# motor_board.net
KiCad netlist of a schematic drawn in EAGLE
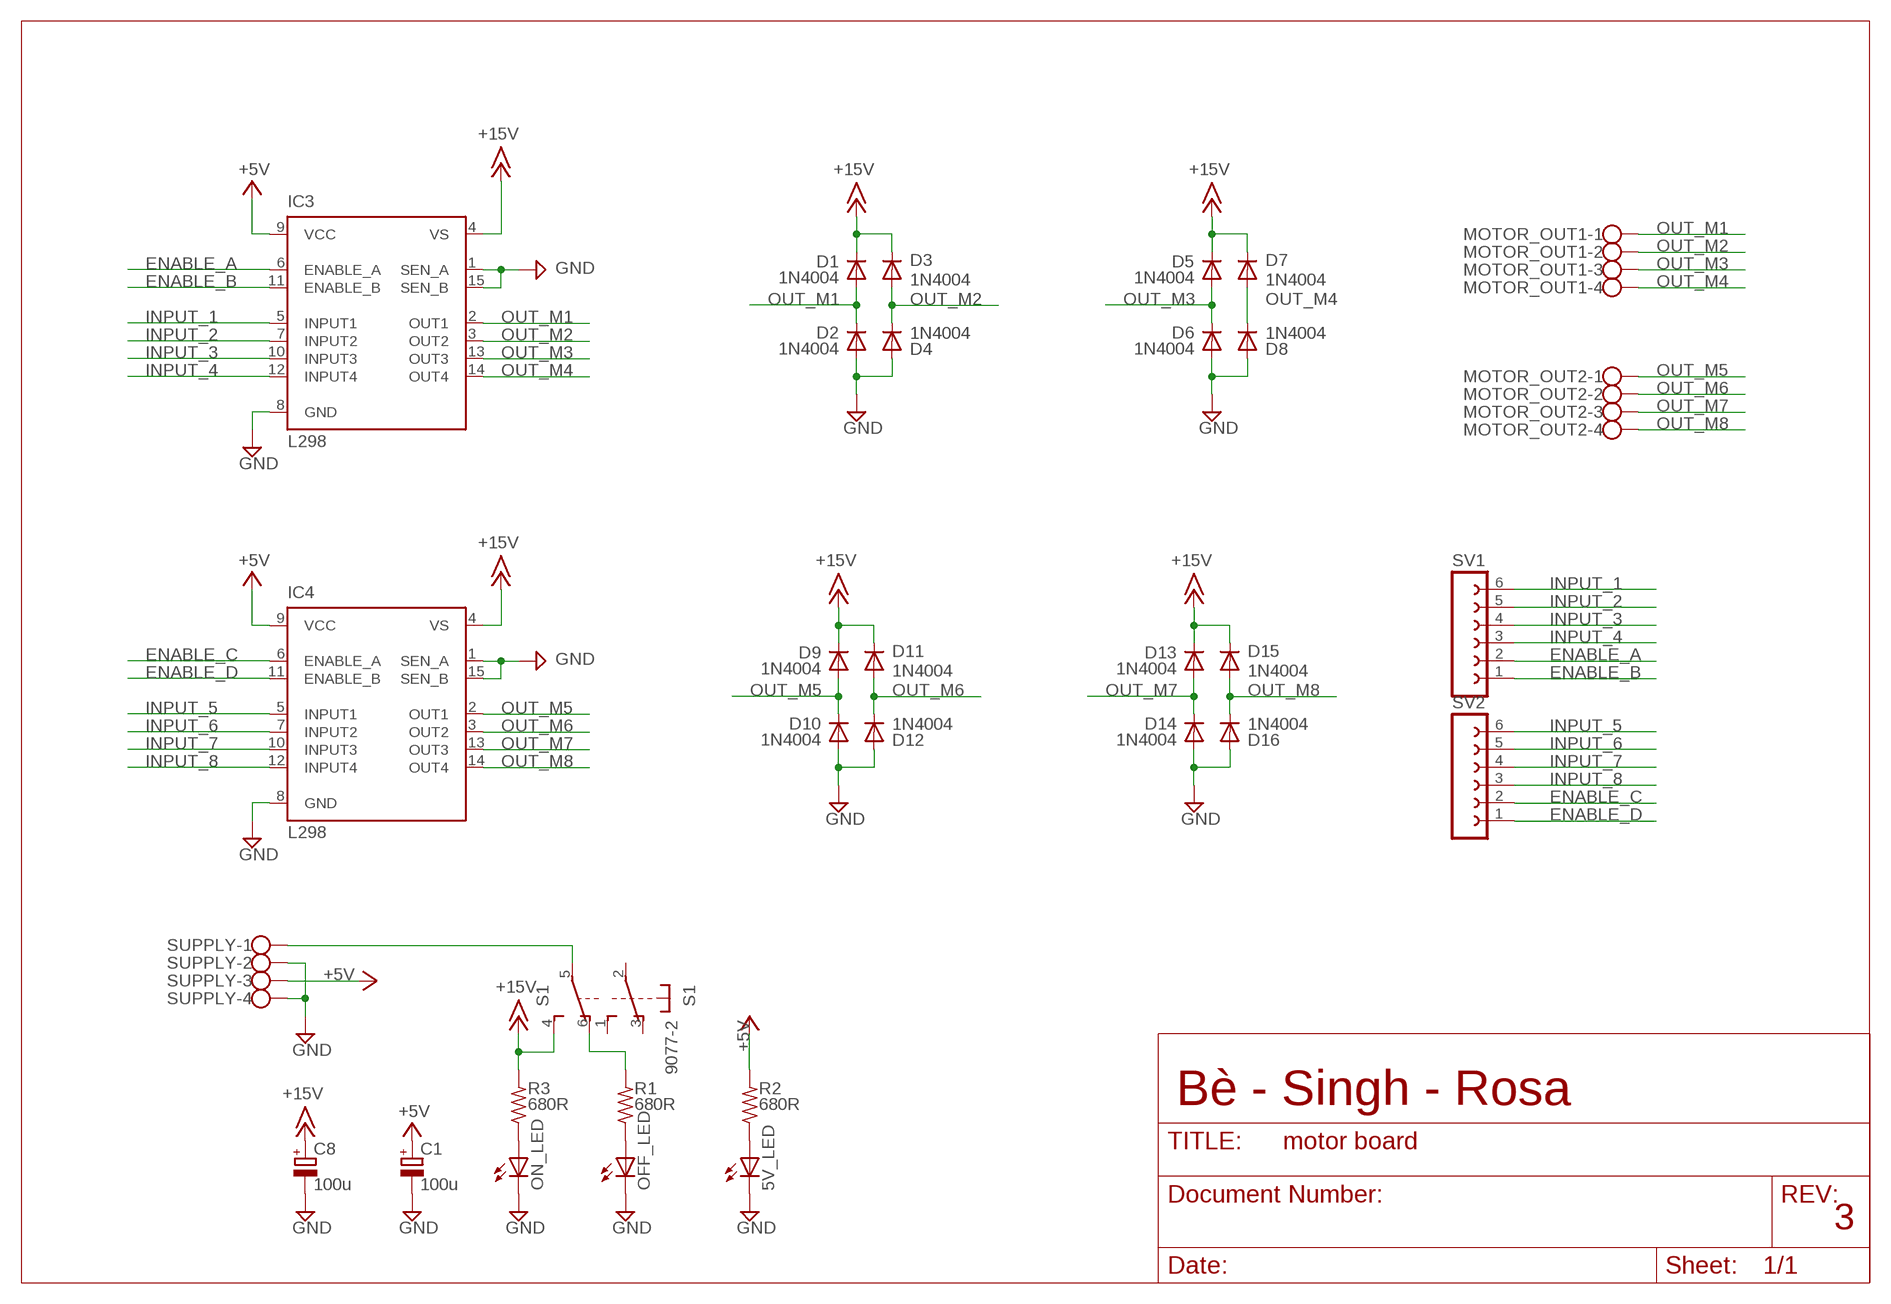
[diagram p0: schematic, sheet 1]

(export (version "E")
  (design (tool "Eeschema 10.0.6"))
  (components
    (comp (ref "5V_LED")
      (value "LED5MM")
      (footprint "eagle-import:LED5MM")
      (libsource (lib "eagle-import") (part "LED5MM"))
    )
    (comp (ref "C1")
      (value "100u")
      (footprint "eagle-import:E2,5-7")
      (libsource (lib "eagle-import") (part "CPOL-EUE2.5-7"))
    )
    (comp (ref "C8")
      (value "100u")
      (footprint "eagle-import:E3,5-8")
      (libsource (lib "eagle-import") (part "rcl_CPOL-EUE3.5-8"))
    )
    (comp (ref "D1")
      (value "1N4004")
      (footprint "eagle-import:DO41-10")
      (libsource (lib "eagle-import") (part "1N4004"))
    )
    (comp (ref "D2")
      (value "1N4004")
      (footprint "eagle-import:DO41-10")
      (libsource (lib "eagle-import") (part "1N4004"))
    )
    (comp (ref "D3")
      (value "1N4004")
      (footprint "eagle-import:DO41-10")
      (libsource (lib "eagle-import") (part "1N4004"))
    )
    (comp (ref "D4")
      (value "1N4004")
      (footprint "eagle-import:DO41-10")
      (libsource (lib "eagle-import") (part "1N4004"))
    )
    (comp (ref "D5")
      (value "1N4004")
      (footprint "eagle-import:DO41-10")
      (libsource (lib "eagle-import") (part "1N4004"))
    )
    (comp (ref "D6")
      (value "1N4004")
      (footprint "eagle-import:DO41-10")
      (libsource (lib "eagle-import") (part "1N4004"))
    )
    (comp (ref "D7")
      (value "1N4004")
      (footprint "eagle-import:DO41-10")
      (libsource (lib "eagle-import") (part "1N4004"))
    )
    (comp (ref "D8")
      (value "1N4004")
      (footprint "eagle-import:DO41-10")
      (libsource (lib "eagle-import") (part "1N4004"))
    )
    (comp (ref "D9")
      (value "1N4004")
      (footprint "eagle-import:DO41-10")
      (libsource (lib "eagle-import") (part "1N4004"))
    )
    (comp (ref "D10")
      (value "1N4004")
      (footprint "eagle-import:DO41-10")
      (libsource (lib "eagle-import") (part "1N4004"))
    )
    (comp (ref "D11")
      (value "1N4004")
      (footprint "eagle-import:DO41-10")
      (libsource (lib "eagle-import") (part "1N4004"))
    )
    (comp (ref "D12")
      (value "1N4004")
      (footprint "eagle-import:DO41-10")
      (libsource (lib "eagle-import") (part "1N4004"))
    )
    (comp (ref "D13")
      (value "1N4004")
      (footprint "eagle-import:DO41-10")
      (libsource (lib "eagle-import") (part "1N4004"))
    )
    (comp (ref "D14")
      (value "1N4004")
      (footprint "eagle-import:DO41-10")
      (libsource (lib "eagle-import") (part "1N4004"))
    )
    (comp (ref "D15")
      (value "1N4004")
      (footprint "eagle-import:DO41-10")
      (libsource (lib "eagle-import") (part "1N4004"))
    )
    (comp (ref "D16")
      (value "1N4004")
      (footprint "eagle-import:DO41-10")
      (libsource (lib "eagle-import") (part "1N4004"))
    )
    (comp (ref "IC3")
      (value "L298")
      (footprint "eagle-import:MULTIWATT-15")
      (libsource (lib "eagle-import") (part "L298"))
    )
    (comp (ref "IC4")
      (value "L298")
      (footprint "eagle-import:MULTIWATT-15")
      (libsource (lib "eagle-import") (part "L298"))
    )
    (comp (ref "MOTOR_OUT1")
      (value "W237-4")
      (footprint "eagle-import:W237-4")
      (libsource (lib "eagle-import") (part "W237-4"))
    )
    (comp (ref "MOTOR_OUT2")
      (value "W237-4")
      (footprint "eagle-import:W237-4")
      (libsource (lib "eagle-import") (part "W237-4"))
    )
    (comp (ref "OFF_LED")
      (value "LED5MM")
      (footprint "eagle-import:LED5MM")
      (libsource (lib "eagle-import") (part "LED5MM"))
    )
    (comp (ref "ON_LED")
      (value "LED5MM")
      (footprint "eagle-import:LED5MM")
      (libsource (lib "eagle-import") (part "LED5MM"))
    )
    (comp (ref "R1")
      (value "680R")
      (footprint "eagle-import:0207_10")
      (libsource (lib "eagle-import") (part "R-US_0207/10"))
    )
    (comp (ref "R2")
      (value "680R")
      (footprint "eagle-import:0207_10")
      (libsource (lib "eagle-import") (part "R-US_0207/10"))
    )
    (comp (ref "R3")
      (value "680R")
      (footprint "eagle-import:0207_10")
      (libsource (lib "eagle-import") (part "R-US_0207/10"))
    )
    (comp (ref "S1")
      (value "9077-2")
      (footprint "eagle-import:9077-2")
      (libsource (lib "eagle-import") (part "9077-2"))
    )
    (comp (ref "SUPPLY")
      (value "W237-4")
      (footprint "eagle-import:W237-4")
      (libsource (lib "eagle-import") (part "W237-4"))
    )
    (comp (ref "SV1")
      (value "FE06-1")
      (footprint "eagle-import:FE06")
      (libsource (lib "eagle-import") (part "FE06-1"))
    )
    (comp (ref "SV2")
      (value "FE06-1")
      (footprint "eagle-import:FE06")
      (libsource (lib "eagle-import") (part "FE06-1"))
    )
  )
  (nets
    (net (code "1") (name "+5V") (class "Default")
      (node (ref "C1") (pin "+") (pinfunction "+_+") (pintype "passive"))
      (node (ref "IC3") (pin "9") (pinfunction "VCC_9") (pintype "power_in"))
      (node (ref "IC4") (pin "9") (pinfunction "VCC_9") (pintype "power_in"))
      (node (ref "R2") (pin "2") (pinfunction "2_2") (pintype "passive"))
      (node (ref "SUPPLY") (pin "3") (pinfunction "KL_3") (pintype "passive"))
    )
    (net (code "2") (name "+15V") (class "Default")
      (node (ref "C8") (pin "+") (pinfunction "+_+") (pintype "passive"))
      (node (ref "D1") (pin "C") (pinfunction "C_C") (pintype "passive"))
      (node (ref "D11") (pin "C") (pinfunction "C_C") (pintype "passive"))
      (node (ref "D13") (pin "C") (pinfunction "C_C") (pintype "passive"))
      (node (ref "D15") (pin "C") (pinfunction "C_C") (pintype "passive"))
      (node (ref "D3") (pin "C") (pinfunction "C_C") (pintype "passive"))
      (node (ref "D5") (pin "C") (pinfunction "C_C") (pintype "passive"))
      (node (ref "D7") (pin "C") (pinfunction "C_C") (pintype "passive"))
      (node (ref "D9") (pin "C") (pinfunction "C_C") (pintype "passive"))
      (node (ref "IC3") (pin "4") (pinfunction "VS_4") (pintype "power_in"))
      (node (ref "IC4") (pin "4") (pinfunction "VS_4") (pintype "power_in"))
      (node (ref "R3") (pin "2") (pinfunction "2_2") (pintype "passive"))
      (node (ref "S1") (pin "4") (pinfunction "S_4") (pintype "passive"))
    )
    (net (code "3") (name "/ENABLE_A") (class "Default")
      (node (ref "IC3") (pin "6") (pinfunction "ENABLE_A_6") (pintype "input"))
      (node (ref "SV1") (pin "2") (pinfunction "2_2") (pintype "passive"))
    )
    (net (code "4") (name "/ENABLE_B") (class "Default")
      (node (ref "IC3") (pin "11") (pinfunction "ENABLE_B_11") (pintype "input"))
      (node (ref "SV1") (pin "1") (pinfunction "1_1") (pintype "passive"))
    )
    (net (code "5") (name "/ENABLE_C") (class "Default")
      (node (ref "IC4") (pin "6") (pinfunction "ENABLE_A_6") (pintype "input"))
      (node (ref "SV2") (pin "2") (pinfunction "2_2") (pintype "passive"))
    )
    (net (code "6") (name "/ENABLE_D") (class "Default")
      (node (ref "IC4") (pin "11") (pinfunction "ENABLE_B_11") (pintype "input"))
      (node (ref "SV2") (pin "1") (pinfunction "1_1") (pintype "passive"))
    )
    (net (code "7") (name "/INPUT_1") (class "Default")
      (node (ref "IC3") (pin "5") (pinfunction "INPUT1_5") (pintype "input"))
      (node (ref "SV1") (pin "6") (pinfunction "6_6") (pintype "passive"))
    )
    (net (code "8") (name "/INPUT_2") (class "Default")
      (node (ref "IC3") (pin "7") (pinfunction "INPUT2_7") (pintype "input"))
      (node (ref "SV1") (pin "5") (pinfunction "5_5") (pintype "passive"))
    )
    (net (code "9") (name "/INPUT_3") (class "Default")
      (node (ref "IC3") (pin "10") (pinfunction "INPUT3_10") (pintype "input"))
      (node (ref "SV1") (pin "4") (pinfunction "4_4") (pintype "passive"))
    )
    (net (code "10") (name "/INPUT_4") (class "Default")
      (node (ref "IC3") (pin "12") (pinfunction "INPUT4_12") (pintype "input"))
      (node (ref "SV1") (pin "3") (pinfunction "3_3") (pintype "passive"))
    )
    (net (code "11") (name "/INPUT_5") (class "Default")
      (node (ref "IC4") (pin "5") (pinfunction "INPUT1_5") (pintype "input"))
      (node (ref "SV2") (pin "6") (pinfunction "6_6") (pintype "passive"))
    )
    (net (code "12") (name "/INPUT_6") (class "Default")
      (node (ref "IC4") (pin "7") (pinfunction "INPUT2_7") (pintype "input"))
      (node (ref "SV2") (pin "5") (pinfunction "5_5") (pintype "passive"))
    )
    (net (code "13") (name "/INPUT_7") (class "Default")
      (node (ref "IC4") (pin "10") (pinfunction "INPUT3_10") (pintype "input"))
      (node (ref "SV2") (pin "4") (pinfunction "4_4") (pintype "passive"))
    )
    (net (code "14") (name "/INPUT_8") (class "Default")
      (node (ref "IC4") (pin "12") (pinfunction "INPUT4_12") (pintype "input"))
      (node (ref "SV2") (pin "3") (pinfunction "3_3") (pintype "passive"))
    )
    (net (code "15") (name "/OUT_M1") (class "Default")
      (node (ref "D1") (pin "A") (pinfunction "A_A") (pintype "passive"))
      (node (ref "D2") (pin "C") (pinfunction "C_C") (pintype "passive"))
      (node (ref "IC3") (pin "2") (pinfunction "OUT1_2") (pintype "output"))
      (node (ref "MOTOR_OUT1") (pin "1") (pinfunction "KL_1") (pintype "passive"))
    )
    (net (code "16") (name "/OUT_M2") (class "Default")
      (node (ref "D3") (pin "A") (pinfunction "A_A") (pintype "passive"))
      (node (ref "D4") (pin "C") (pinfunction "C_C") (pintype "passive"))
      (node (ref "IC3") (pin "3") (pinfunction "OUT2_3") (pintype "output"))
      (node (ref "MOTOR_OUT1") (pin "2") (pinfunction "KL_2") (pintype "passive"))
    )
    (net (code "17") (name "/OUT_M3") (class "Default")
      (node (ref "D5") (pin "A") (pinfunction "A_A") (pintype "passive"))
      (node (ref "D6") (pin "C") (pinfunction "C_C") (pintype "passive"))
      (node (ref "IC3") (pin "13") (pinfunction "OUT3_13") (pintype "output"))
      (node (ref "MOTOR_OUT1") (pin "3") (pinfunction "KL_3") (pintype "passive"))
    )
    (net (code "18") (name "/OUT_M4") (class "Default")
      (node (ref "D7") (pin "A") (pinfunction "A_A") (pintype "passive"))
      (node (ref "D8") (pin "C") (pinfunction "C_C") (pintype "passive"))
      (node (ref "IC3") (pin "14") (pinfunction "OUT4_14") (pintype "output"))
      (node (ref "MOTOR_OUT1") (pin "4") (pinfunction "KL_4") (pintype "passive"))
    )
    (net (code "19") (name "/OUT_M5") (class "Default")
      (node (ref "D10") (pin "C") (pinfunction "C_C") (pintype "passive"))
      (node (ref "D9") (pin "A") (pinfunction "A_A") (pintype "passive"))
      (node (ref "IC4") (pin "2") (pinfunction "OUT1_2") (pintype "output"))
      (node (ref "MOTOR_OUT2") (pin "1") (pinfunction "KL_1") (pintype "passive"))
    )
    (net (code "20") (name "/OUT_M6") (class "Default")
      (node (ref "D11") (pin "A") (pinfunction "A_A") (pintype "passive"))
      (node (ref "D12") (pin "C") (pinfunction "C_C") (pintype "passive"))
      (node (ref "IC4") (pin "3") (pinfunction "OUT2_3") (pintype "output"))
      (node (ref "MOTOR_OUT2") (pin "2") (pinfunction "KL_2") (pintype "passive"))
    )
    (net (code "21") (name "/OUT_M7") (class "Default")
      (node (ref "D13") (pin "A") (pinfunction "A_A") (pintype "passive"))
      (node (ref "D14") (pin "C") (pinfunction "C_C") (pintype "passive"))
      (node (ref "IC4") (pin "13") (pinfunction "OUT3_13") (pintype "output"))
      (node (ref "MOTOR_OUT2") (pin "3") (pinfunction "KL_3") (pintype "passive"))
    )
    (net (code "22") (name "/OUT_M8") (class "Default")
      (node (ref "D15") (pin "A") (pinfunction "A_A") (pintype "passive"))
      (node (ref "D16") (pin "C") (pinfunction "C_C") (pintype "passive"))
      (node (ref "IC4") (pin "14") (pinfunction "OUT4_14") (pintype "output"))
      (node (ref "MOTOR_OUT2") (pin "4") (pinfunction "KL_4") (pintype "passive"))
    )
    (net (code "23") (name "GND") (class "Default")
      (node (ref "5V_LED") (pin "K") (pinfunction "C_K") (pintype "passive"))
      (node (ref "C1") (pin "-") (pinfunction "-_-") (pintype "passive"))
      (node (ref "C8") (pin "-") (pinfunction "-_-") (pintype "passive"))
      (node (ref "D10") (pin "A") (pinfunction "A_A") (pintype "passive"))
      (node (ref "D12") (pin "A") (pinfunction "A_A") (pintype "passive"))
      (node (ref "D14") (pin "A") (pinfunction "A_A") (pintype "passive"))
      (node (ref "D16") (pin "A") (pinfunction "A_A") (pintype "passive"))
      (node (ref "D2") (pin "A") (pinfunction "A_A") (pintype "passive"))
      (node (ref "D4") (pin "A") (pinfunction "A_A") (pintype "passive"))
      (node (ref "D6") (pin "A") (pinfunction "A_A") (pintype "passive"))
      (node (ref "D8") (pin "A") (pinfunction "A_A") (pintype "passive"))
      (node (ref "IC3") (pin "1") (pinfunction "SEN_A_1") (pintype "input"))
      (node (ref "IC3") (pin "15") (pinfunction "SEN_B_15") (pintype "input"))
      (node (ref "IC3") (pin "8") (pinfunction "GND_8") (pintype "power_in"))
      (node (ref "IC4") (pin "1") (pinfunction "SEN_A_1") (pintype "input"))
      (node (ref "IC4") (pin "15") (pinfunction "SEN_B_15") (pintype "input"))
      (node (ref "IC4") (pin "8") (pinfunction "GND_8") (pintype "power_in"))
      (node (ref "OFF_LED") (pin "K") (pinfunction "C_K") (pintype "passive"))
      (node (ref "ON_LED") (pin "K") (pinfunction "C_K") (pintype "passive"))
      (node (ref "SUPPLY") (pin "2") (pinfunction "KL_2") (pintype "passive"))
      (node (ref "SUPPLY") (pin "4") (pinfunction "KL_4") (pintype "passive"))
    )
    (net (code "24") (name "Net-(5V_LED-PadA)") (class "Default")
      (node (ref "5V_LED") (pin "A") (pinfunction "A_A") (pintype "passive"))
      (node (ref "R2") (pin "1") (pinfunction "1_1") (pintype "passive"))
    )
    (net (code "25") (name "Net-(OFF_LED-PadA)") (class "Default")
      (node (ref "OFF_LED") (pin "A") (pinfunction "A_A") (pintype "passive"))
      (node (ref "R1") (pin "1") (pinfunction "1_1") (pintype "passive"))
    )
    (net (code "26") (name "Net-(ON_LED-PadA)") (class "Default")
      (node (ref "ON_LED") (pin "A") (pinfunction "A_A") (pintype "passive"))
      (node (ref "R3") (pin "1") (pinfunction "1_1") (pintype "passive"))
    )
    (net (code "27") (name "Net-(S1B-O)") (class "Default")
      (node (ref "R1") (pin "2") (pinfunction "2_2") (pintype "passive"))
      (node (ref "S1") (pin "6") (pinfunction "O_6") (pintype "passive"))
    )
    (net (code "28") (name "Net-(S1B-P)") (class "Default")
      (node (ref "S1") (pin "5") (pinfunction "P_5") (pintype "passive"))
      (node (ref "SUPPLY") (pin "1") (pinfunction "KL_1") (pintype "passive"))
    )
    (net (code "29") (name "unconnected-(S1A-O-Pad3)") (class "Default")
      (node (ref "S1") (pin "3") (pinfunction "O_3") (pintype "passive"))
    )
    (net (code "30") (name "unconnected-(S1A-P-Pad2)") (class "Default")
      (node (ref "S1") (pin "2") (pinfunction "P_2") (pintype "passive"))
    )
    (net (code "31") (name "unconnected-(S1A-S-Pad1)") (class "Default")
      (node (ref "S1") (pin "1") (pinfunction "S_1") (pintype "passive"))
    )
  )
)
